# sim800c_gsm_dev_board.net
KiCad netlist of a schematic drawn in EAGLE
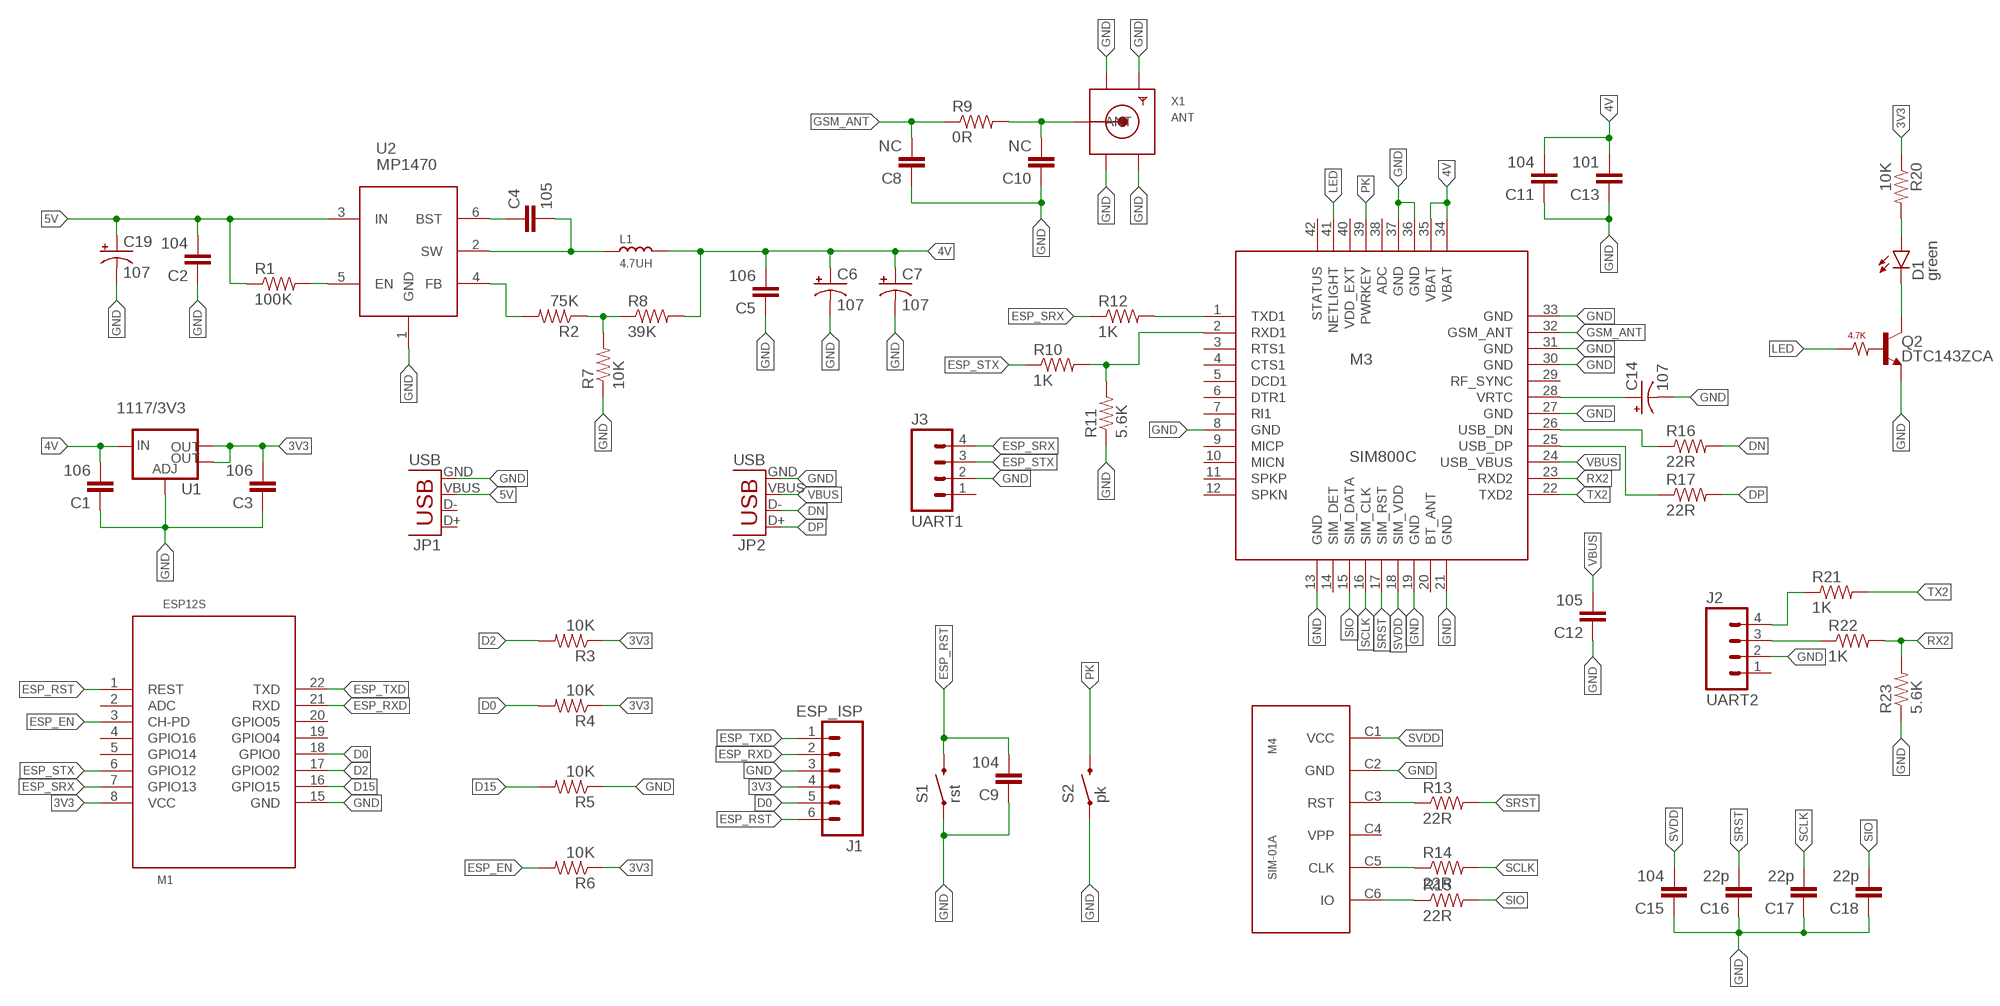
[diagram p0: schematic, sheet 1]

(export (version "E")
  (design (tool "Eeschema 10.0.6"))
  (components
    (comp (ref "C1")
      (value "106")
      (footprint "eagle-import:0603-CAP")
      (libsource (lib "eagle-import") (part "CAP0603-CAP"))
    )
    (comp (ref "C2")
      (value "104")
      (footprint "eagle-import:0603-CAP")
      (libsource (lib "eagle-import") (part "CAP0603-CAP"))
    )
    (comp (ref "C3")
      (value "106")
      (footprint "eagle-import:0603-CAP")
      (libsource (lib "eagle-import") (part "CAP0603-CAP"))
    )
    (comp (ref "C4")
      (value "105")
      (footprint "eagle-import:0603-CAP")
      (libsource (lib "eagle-import") (part "CAP0603-CAP"))
    )
    (comp (ref "C5")
      (value "106")
      (footprint "eagle-import:0603-CAP")
      (libsource (lib "eagle-import") (part "CAP0603-CAP"))
    )
    (comp (ref "C6")
      (value "107")
      (footprint "eagle-import:EIA3528")
      (libsource (lib "eagle-import") (part "CAP_POL3528"))
    )
    (comp (ref "C7")
      (value "107")
      (footprint "eagle-import:EIA3528")
      (libsource (lib "eagle-import") (part "CAP_POL3528"))
    )
    (comp (ref "C8")
      (value "NC")
      (footprint "eagle-import:C0402")
      (libsource (lib "eagle-import") (part "CAP-SEEED-0402"))
    )
    (comp (ref "C9")
      (value "104")
      (footprint "eagle-import:C0402")
      (libsource (lib "eagle-import") (part "CAP-SEEED-0402"))
    )
    (comp (ref "C10")
      (value "NC")
      (footprint "eagle-import:C0402")
      (libsource (lib "eagle-import") (part "CAP-SEEED-0402"))
    )
    (comp (ref "C11")
      (value "104")
      (footprint "eagle-import:C0402")
      (libsource (lib "eagle-import") (part "CAP-SEEED-0402"))
    )
    (comp (ref "C12")
      (value "105")
      (footprint "eagle-import:0603-CAP")
      (libsource (lib "eagle-import") (part "CAP0603-CAP"))
    )
    (comp (ref "C13")
      (value "101")
      (footprint "eagle-import:C0402")
      (libsource (lib "eagle-import") (part "CAP-SEEED-0402"))
    )
    (comp (ref "C14")
      (value "107")
      (footprint "eagle-import:EIA3528")
      (libsource (lib "eagle-import") (part "CAP_POL3528"))
    )
    (comp (ref "C15")
      (value "104")
      (footprint "eagle-import:C0402")
      (libsource (lib "eagle-import") (part "CAP-SEEED-0402"))
    )
    (comp (ref "C16")
      (value "22p")
      (footprint "eagle-import:C0402")
      (libsource (lib "eagle-import") (part "CAP-SEEED-0402"))
    )
    (comp (ref "C17")
      (value "22p")
      (footprint "eagle-import:C0402")
      (libsource (lib "eagle-import") (part "CAP-SEEED-0402"))
    )
    (comp (ref "C18")
      (value "22p")
      (footprint "eagle-import:C0402")
      (libsource (lib "eagle-import") (part "CAP-SEEED-0402"))
    )
    (comp (ref "C19")
      (value "107")
      (footprint "eagle-import:EIA3528")
      (libsource (lib "eagle-import") (part "CAP_POL3528"))
    )
    (comp (ref "D1")
      (value "green")
      (footprint "eagle-import:LED-0603-SEEED")
      (libsource (lib "eagle-import") (part "LED-SEEED-0603"))
    )
    (comp (ref "J1")
      (value "ESP_ISP")
      (footprint "eagle-import:1X06_NO_SILK")
      (libsource (lib "eagle-import") (part "M06NO_SILK_FEMALE_PTH"))
    )
    (comp (ref "J2")
      (value "UART2")
      (footprint "eagle-import:1X04_NO_SILK_ALL_ROUND")
      (libsource (lib "eagle-import") (part "M04NO_SILK_ALL_ROUND"))
    )
    (comp (ref "J3")
      (value "UART1")
      (footprint "eagle-import:1X04_NO_SILK_ALL_ROUND")
      (libsource (lib "eagle-import") (part "M04NO_SILK_ALL_ROUND"))
    )
    (comp (ref "JP1")
      (value "USB")
      (footprint "eagle-import:MICROUSB-U-F-M5DD-Y-1")
      (libsource (lib "eagle-import") (part "USB"))
    )
    (comp (ref "JP2")
      (value "USB")
      (footprint "eagle-import:MICROUSB-U-F-M5DD-Y-1")
      (libsource (lib "eagle-import") (part "USB"))
    )
    (comp (ref "L1")
      (value "4.7UH")
      (footprint "eagle-import:SMD-2P-5.0X5.0X2.0MM")
      (fields (field (name "MPN") "SWPA5020S220MT"))
      (libsource (lib "eagle-import") (part "SMD-INDUCTOR-200UH-20%(2P-5X5MM)"))
    )
    (comp (ref "M1")
      (value "ESP12S")
      (footprint "eagle-import:LGA22-2.0-24X16MM-SIMPLE")
      (libsource (lib "eagle-import") (part "MODULE-WIFI-ESP8266-12E-SIMPLE"))
    )
    (comp (ref "M3")
      (value "SIM800C")
      (footprint "eagle-import:SIM800C")
      (libsource (lib "eagle-import") (part "SIM800C"))
    )
    (comp (ref "M4")
      (value "SIM-01A")
      (footprint "eagle-import:SIM-01A")
      (libsource (lib "eagle-import") (part "SIM-01A"))
    )
    (comp (ref "Q2")
      (value "DTC143ZCA")
      (footprint "eagle-import:SOT23-3")
      (libsource (lib "eagle-import") (part "TRANS_NPN_RES-DDTD142TC-7-F"))
    )
    (comp (ref "R1")
      (value "100K")
      (footprint "eagle-import:R0402")
      (libsource (lib "eagle-import") (part "RESISTOR-SEEED-0402"))
    )
    (comp (ref "R2")
      (value "75K")
      (footprint "eagle-import:R0402")
      (libsource (lib "eagle-import") (part "RESISTOR-SEEED-0402"))
    )
    (comp (ref "R3")
      (value "10K")
      (footprint "eagle-import:R0402")
      (libsource (lib "eagle-import") (part "RESISTOR-SEEED-0402"))
    )
    (comp (ref "R4")
      (value "10K")
      (footprint "eagle-import:R0402")
      (libsource (lib "eagle-import") (part "RESISTOR-SEEED-0402"))
    )
    (comp (ref "R5")
      (value "10K")
      (footprint "eagle-import:R0402")
      (libsource (lib "eagle-import") (part "RESISTOR-SEEED-0402"))
    )
    (comp (ref "R6")
      (value "10K")
      (footprint "eagle-import:R0402")
      (libsource (lib "eagle-import") (part "RESISTOR-SEEED-0402"))
    )
    (comp (ref "R7")
      (value "10K")
      (footprint "eagle-import:R0402")
      (libsource (lib "eagle-import") (part "RESISTOR-SEEED-0402"))
    )
    (comp (ref "R8")
      (value "39K")
      (footprint "eagle-import:R0402")
      (libsource (lib "eagle-import") (part "RESISTOR-SEEED-0402"))
    )
    (comp (ref "R9")
      (value "0R")
      (footprint "eagle-import:R0402")
      (libsource (lib "eagle-import") (part "RESISTOR-SEEED-0402"))
    )
    (comp (ref "R10")
      (value "1K")
      (footprint "eagle-import:R0402")
      (libsource (lib "eagle-import") (part "RESISTOR-SEEED-0402"))
    )
    (comp (ref "R11")
      (value "5.6K")
      (footprint "eagle-import:R0402")
      (libsource (lib "eagle-import") (part "RESISTOR-SEEED-0402"))
    )
    (comp (ref "R12")
      (value "1K")
      (footprint "eagle-import:R0402")
      (libsource (lib "eagle-import") (part "RESISTOR-SEEED-0402"))
    )
    (comp (ref "R13")
      (value "22R")
      (footprint "eagle-import:R0402")
      (libsource (lib "eagle-import") (part "RESISTOR-SEEED-0402"))
    )
    (comp (ref "R14")
      (value "22R")
      (footprint "eagle-import:R0402")
      (libsource (lib "eagle-import") (part "RESISTOR-SEEED-0402"))
    )
    (comp (ref "R15")
      (value "22R")
      (footprint "eagle-import:R0402")
      (libsource (lib "eagle-import") (part "RESISTOR-SEEED-0402"))
    )
    (comp (ref "R16")
      (value "22R")
      (footprint "eagle-import:R0402")
      (libsource (lib "eagle-import") (part "RESISTOR-SEEED-0402"))
    )
    (comp (ref "R17")
      (value "22R")
      (footprint "eagle-import:R0402")
      (libsource (lib "eagle-import") (part "RESISTOR-SEEED-0402"))
    )
    (comp (ref "R20")
      (value "10K")
      (footprint "eagle-import:R0402")
      (libsource (lib "eagle-import") (part "RESISTOR-SEEED-0402"))
    )
    (comp (ref "R21")
      (value "1K")
      (footprint "eagle-import:R0402")
      (libsource (lib "eagle-import") (part "RESISTOR-SEEED-0402"))
    )
    (comp (ref "R22")
      (value "1K")
      (footprint "eagle-import:R0402")
      (libsource (lib "eagle-import") (part "RESISTOR-SEEED-0402"))
    )
    (comp (ref "R23")
      (value "5.6K")
      (footprint "eagle-import:R0402")
      (libsource (lib "eagle-import") (part "RESISTOR-SEEED-0402"))
    )
    (comp (ref "S1")
      (value "rst")
      (footprint "eagle-import:TACTILE_SWITCH_TALL")
      (libsource (lib "eagle-import") (part "SWITCH-MOMENTARY-2SMD-4"))
    )
    (comp (ref "S2")
      (value "pk")
      (footprint "eagle-import:TACTILE_SWITCH_TALL")
      (libsource (lib "eagle-import") (part "SWITCH-MOMENTARY-2SMD-4"))
    )
    (comp (ref "U1")
      (value "1117/3V3")
      (footprint "eagle-import:SOT223")
      (libsource (lib "eagle-import") (part "AMS1117SOT223"))
    )
    (comp (ref "U2")
      (value "MP1470")
      (footprint "eagle-import:SOT23-6")
      (libsource (lib "eagle-import") (part "MP1470"))
    )
    (comp (ref "X1")
      (value "ANT")
      (footprint "eagle-import:SMA90_DIP")
      (libsource (lib "eagle-import") (part "SMACONNECTOR"))
    )
  )
  (nets
    (net (code "1") (name "3V3") (class "Default")
      (node (ref "C3") (pin "2") (pinfunction "2_2") (pintype "passive"))
      (node (ref "J1") (pin "4") (pinfunction "4_4") (pintype "passive"))
      (node (ref "M1") (pin "8") (pinfunction "VCC_8") (pintype "bidirectional"))
      (node (ref "R20") (pin "1") (pinfunction "1_1") (pintype "passive"))
      (node (ref "R3") (pin "1") (pinfunction "1_1") (pintype "passive"))
      (node (ref "R4") (pin "1") (pinfunction "1_1") (pintype "passive"))
      (node (ref "R6") (pin "1") (pinfunction "1_1") (pintype "passive"))
      (node (ref "U1") (pin "2") (pinfunction "OUT_2") (pintype "output"))
      (node (ref "U1") (pin "4") (pinfunction "OUT_4") (pintype "output"))
    )
    (net (code "2") (name "4V") (class "Default")
      (node (ref "C1") (pin "2") (pinfunction "2_2") (pintype "passive"))
      (node (ref "C11") (pin "2") (pinfunction "2_2") (pintype "passive"))
      (node (ref "C13") (pin "2") (pinfunction "2_2") (pintype "passive"))
      (node (ref "C5") (pin "2") (pinfunction "2_2") (pintype "passive"))
      (node (ref "C6") (pin "A") (pinfunction "+_A") (pintype "passive"))
      (node (ref "C7") (pin "A") (pinfunction "+_A") (pintype "passive"))
      (node (ref "L1") (pin "2") (pinfunction "2_2") (pintype "passive"))
      (node (ref "M3") (pin "34") (pinfunction "VBAT_34") (pintype "bidirectional"))
      (node (ref "M3") (pin "35") (pinfunction "VBAT_35") (pintype "bidirectional"))
      (node (ref "R8") (pin "2") (pinfunction "2_2") (pintype "passive"))
      (node (ref "U1") (pin "3") (pinfunction "IN_3") (pintype "input"))
    )
    (net (code "3") (name "5V") (class "Default")
      (node (ref "C19") (pin "A") (pinfunction "+_A") (pintype "passive"))
      (node (ref "C2") (pin "2") (pinfunction "2_2") (pintype "passive"))
      (node (ref "JP1") (pin "VBUS") (pinfunction "VBUS_VBUS") (pintype "bidirectional"))
      (node (ref "R1") (pin "1") (pinfunction "1_1") (pintype "passive"))
      (node (ref "U2") (pin "3") (pinfunction "IN_3") (pintype "bidirectional"))
    )
    (net (code "4") (name "D0") (class "Default")
      (node (ref "J1") (pin "5") (pinfunction "5_5") (pintype "passive"))
      (node (ref "M1") (pin "18") (pinfunction "GPIO0_18") (pintype "bidirectional"))
      (node (ref "R4") (pin "2") (pinfunction "2_2") (pintype "passive"))
    )
    (net (code "5") (name "D2") (class "Default")
      (node (ref "M1") (pin "17") (pinfunction "GPIO02_17") (pintype "bidirectional"))
      (node (ref "R3") (pin "2") (pinfunction "2_2") (pintype "passive"))
    )
    (net (code "6") (name "D15") (class "Default")
      (node (ref "M1") (pin "16") (pinfunction "GPIO15_16") (pintype "bidirectional"))
      (node (ref "R5") (pin "2") (pinfunction "2_2") (pintype "passive"))
    )
    (net (code "7") (name "DN") (class "Default")
      (node (ref "JP2") (pin "D-") (pinfunction "D-_D-") (pintype "bidirectional"))
      (node (ref "R16") (pin "2") (pinfunction "2_2") (pintype "passive"))
    )
    (net (code "8") (name "DP") (class "Default")
      (node (ref "JP2") (pin "D+") (pinfunction "D+_D+") (pintype "bidirectional"))
      (node (ref "R17") (pin "2") (pinfunction "2_2") (pintype "passive"))
    )
    (net (code "9") (name "ESP_EN") (class "Default")
      (node (ref "M1") (pin "3") (pinfunction "CH-PD_3") (pintype "bidirectional"))
      (node (ref "R6") (pin "2") (pinfunction "2_2") (pintype "passive"))
    )
    (net (code "10") (name "ESP_RST") (class "Default")
      (node (ref "C9") (pin "2") (pinfunction "2_2") (pintype "passive"))
      (node (ref "J1") (pin "6") (pinfunction "6_6") (pintype "passive"))
      (node (ref "M1") (pin "1") (pinfunction "REST_1") (pintype "bidirectional"))
      (node (ref "S1") (pin "B2") (pinfunction "2_B2") (pintype "passive"))
    )
    (net (code "11") (name "ESP_RXD") (class "Default")
      (node (ref "J1") (pin "2") (pinfunction "2_2") (pintype "passive"))
      (node (ref "M1") (pin "21") (pinfunction "RXD_21") (pintype "bidirectional"))
    )
    (net (code "12") (name "ESP_SRX") (class "Default")
      (node (ref "J3") (pin "4") (pinfunction "4_4") (pintype "passive"))
      (node (ref "M1") (pin "7") (pinfunction "GPIO13_7") (pintype "bidirectional"))
      (node (ref "R12") (pin "1") (pinfunction "1_1") (pintype "passive"))
    )
    (net (code "13") (name "ESP_STX") (class "Default")
      (node (ref "J3") (pin "3") (pinfunction "3_3") (pintype "passive"))
      (node (ref "M1") (pin "6") (pinfunction "GPIO12_6") (pintype "bidirectional"))
      (node (ref "R10") (pin "1") (pinfunction "1_1") (pintype "passive"))
    )
    (net (code "14") (name "ESP_TXD") (class "Default")
      (node (ref "J1") (pin "1") (pinfunction "1_1") (pintype "passive"))
      (node (ref "M1") (pin "22") (pinfunction "TXD_22") (pintype "bidirectional"))
    )
    (net (code "15") (name "GND") (class "Default")
      (node (ref "C1") (pin "1") (pinfunction "1_1") (pintype "passive"))
      (node (ref "C10") (pin "1") (pinfunction "1_1") (pintype "passive"))
      (node (ref "C11") (pin "1") (pinfunction "1_1") (pintype "passive"))
      (node (ref "C12") (pin "1") (pinfunction "1_1") (pintype "passive"))
      (node (ref "C13") (pin "1") (pinfunction "1_1") (pintype "passive"))
      (node (ref "C14") (pin "C") (pinfunction "-_C") (pintype "passive"))
      (node (ref "C15") (pin "1") (pinfunction "1_1") (pintype "passive"))
      (node (ref "C16") (pin "1") (pinfunction "1_1") (pintype "passive"))
      (node (ref "C17") (pin "1") (pinfunction "1_1") (pintype "passive"))
      (node (ref "C18") (pin "1") (pinfunction "1_1") (pintype "passive"))
      (node (ref "C19") (pin "C") (pinfunction "-_C") (pintype "passive"))
      (node (ref "C2") (pin "1") (pinfunction "1_1") (pintype "passive"))
      (node (ref "C3") (pin "1") (pinfunction "1_1") (pintype "passive"))
      (node (ref "C5") (pin "1") (pinfunction "1_1") (pintype "passive"))
      (node (ref "C6") (pin "C") (pinfunction "-_C") (pintype "passive"))
      (node (ref "C7") (pin "C") (pinfunction "-_C") (pintype "passive"))
      (node (ref "C8") (pin "1") (pinfunction "1_1") (pintype "passive"))
      (node (ref "C9") (pin "1") (pinfunction "1_1") (pintype "passive"))
      (node (ref "J1") (pin "3") (pinfunction "3_3") (pintype "passive"))
      (node (ref "J2") (pin "2") (pinfunction "2_2") (pintype "passive"))
      (node (ref "J3") (pin "2") (pinfunction "2_2") (pintype "passive"))
      (node (ref "JP1") (pin "GND") (pinfunction "GND_GND") (pintype "bidirectional"))
      (node (ref "JP2") (pin "GND") (pinfunction "GND_GND") (pintype "bidirectional"))
      (node (ref "M1") (pin "15") (pinfunction "GND_15") (pintype "bidirectional"))
      (node (ref "M3") (pin "13") (pinfunction "GND_13") (pintype "bidirectional"))
      (node (ref "M3") (pin "19") (pinfunction "GND_19") (pintype "bidirectional"))
      (node (ref "M3") (pin "21") (pinfunction "GND_21") (pintype "bidirectional"))
      (node (ref "M3") (pin "27") (pinfunction "GND_27") (pintype "bidirectional"))
      (node (ref "M3") (pin "30") (pinfunction "GND_30") (pintype "bidirectional"))
      (node (ref "M3") (pin "31") (pinfunction "GND_31") (pintype "bidirectional"))
      (node (ref "M3") (pin "33") (pinfunction "GND_33") (pintype "bidirectional"))
      (node (ref "M3") (pin "36") (pinfunction "GND_36") (pintype "bidirectional"))
      (node (ref "M3") (pin "37") (pinfunction "GND_37") (pintype "bidirectional"))
      (node (ref "M3") (pin "8") (pinfunction "GND_8") (pintype "bidirectional"))
      (node (ref "M4") (pin "C2") (pinfunction "GND_C2") (pintype "bidirectional"))
      (node (ref "Q2") (pin "2") (pinfunction "E_2") (pintype "passive"))
      (node (ref "R11") (pin "1") (pinfunction "1_1") (pintype "passive"))
      (node (ref "R23") (pin "1") (pinfunction "1_1") (pintype "passive"))
      (node (ref "R5") (pin "1") (pinfunction "1_1") (pintype "passive"))
      (node (ref "R7") (pin "1") (pinfunction "1_1") (pintype "passive"))
      (node (ref "S1") (pin "A2") (pinfunction "1_A2") (pintype "passive"))
      (node (ref "S2") (pin "A2") (pinfunction "1_A2") (pintype "passive"))
      (node (ref "U1") (pin "1") (pinfunction "ADJ_1") (pintype "input"))
      (node (ref "U2") (pin "1") (pinfunction "GND_1") (pintype "bidirectional"))
      (node (ref "X1") (pin "GND1") (pinfunction "GND1_GND1") (pintype "power_in"))
      (node (ref "X1") (pin "GND2") (pinfunction "GND2_GND2") (pintype "power_in"))
      (node (ref "X1") (pin "GND3") (pinfunction "GND3_GND3") (pintype "power_in"))
      (node (ref "X1") (pin "GND4") (pinfunction "GND4_GND4") (pintype "power_in"))
    )
    (net (code "16") (name "GSM_ANT") (class "Default")
      (node (ref "C8") (pin "2") (pinfunction "2_2") (pintype "passive"))
      (node (ref "M3") (pin "32") (pinfunction "GSM_ANT_32") (pintype "bidirectional"))
      (node (ref "R9") (pin "1") (pinfunction "1_1") (pintype "passive"))
    )
    (net (code "17") (name "LED") (class "Default")
      (node (ref "M3") (pin "41") (pinfunction "NETLIGHT_41") (pintype "bidirectional"))
      (node (ref "Q2") (pin "1") (pinfunction "B_1") (pintype "passive"))
    )
    (net (code "18") (name "Net-(C14-+)") (class "Default")
      (node (ref "C14") (pin "A") (pinfunction "+_A") (pintype "passive"))
      (node (ref "M3") (pin "28") (pinfunction "VRTC_28") (pintype "bidirectional"))
    )
    (net (code "19") (name "Net-(D1-A)") (class "Default")
      (node (ref "D1") (pin "+") (pinfunction "A_+") (pintype "passive"))
      (node (ref "R20") (pin "2") (pinfunction "2_2") (pintype "passive"))
    )
    (net (code "20") (name "Net-(D1-C)") (class "Default")
      (node (ref "D1") (pin "-") (pinfunction "C_-") (pintype "passive"))
      (node (ref "Q2") (pin "3") (pinfunction "C_3") (pintype "passive"))
    )
    (net (code "21") (name "Net-(J2-Pad3)") (class "Default")
      (node (ref "J2") (pin "3") (pinfunction "3_3") (pintype "passive"))
      (node (ref "R22") (pin "1") (pinfunction "1_1") (pintype "passive"))
    )
    (net (code "22") (name "Net-(J2-Pad4)") (class "Default")
      (node (ref "J2") (pin "4") (pinfunction "4_4") (pintype "passive"))
      (node (ref "R21") (pin "1") (pinfunction "1_1") (pintype "passive"))
    )
    (net (code "23") (name "Net-(M3-RXD1)") (class "Default")
      (node (ref "M3") (pin "2") (pinfunction "RXD1_2") (pintype "bidirectional"))
      (node (ref "R10") (pin "2") (pinfunction "2_2") (pintype "passive"))
      (node (ref "R11") (pin "2") (pinfunction "2_2") (pintype "passive"))
    )
    (net (code "24") (name "Net-(M3-TXD1)") (class "Default")
      (node (ref "M3") (pin "1") (pinfunction "TXD1_1") (pintype "bidirectional"))
      (node (ref "R12") (pin "2") (pinfunction "2_2") (pintype "passive"))
    )
    (net (code "25") (name "Net-(M3-USB_DN)") (class "Default")
      (node (ref "M3") (pin "26") (pinfunction "USB_DN_26") (pintype "bidirectional"))
      (node (ref "R16") (pin "1") (pinfunction "1_1") (pintype "passive"))
    )
    (net (code "26") (name "Net-(M3-USB_DP)") (class "Default")
      (node (ref "M3") (pin "25") (pinfunction "USB_DP_25") (pintype "bidirectional"))
      (node (ref "R17") (pin "1") (pinfunction "1_1") (pintype "passive"))
    )
    (net (code "27") (name "Net-(M4-CLK)") (class "Default")
      (node (ref "M4") (pin "C5") (pinfunction "CLK_C5") (pintype "bidirectional"))
      (node (ref "R14") (pin "1") (pinfunction "1_1") (pintype "passive"))
    )
    (net (code "28") (name "Net-(M4-IO)") (class "Default")
      (node (ref "M4") (pin "C6") (pinfunction "IO_C6") (pintype "bidirectional"))
      (node (ref "R15") (pin "1") (pinfunction "1_1") (pintype "passive"))
    )
    (net (code "29") (name "Net-(M4-RST)") (class "Default")
      (node (ref "M4") (pin "C3") (pinfunction "RST_C3") (pintype "bidirectional"))
      (node (ref "R13") (pin "1") (pinfunction "1_1") (pintype "passive"))
    )
    (net (code "30") (name "Net-(R2-Pad1)") (class "Default")
      (node (ref "R2") (pin "1") (pinfunction "1_1") (pintype "passive"))
      (node (ref "R7") (pin "2") (pinfunction "2_2") (pintype "passive"))
      (node (ref "R8") (pin "1") (pinfunction "1_1") (pintype "passive"))
    )
    (net (code "31") (name "Net-(U2-BST)") (class "Default")
      (node (ref "C4") (pin "1") (pinfunction "1_1") (pintype "passive"))
      (node (ref "U2") (pin "6") (pinfunction "BST_6") (pintype "bidirectional"))
    )
    (net (code "32") (name "Net-(U2-EN)") (class "Default")
      (node (ref "R1") (pin "2") (pinfunction "2_2") (pintype "passive"))
      (node (ref "U2") (pin "5") (pinfunction "EN_5") (pintype "bidirectional"))
    )
    (net (code "33") (name "Net-(U2-FB)") (class "Default")
      (node (ref "R2") (pin "2") (pinfunction "2_2") (pintype "passive"))
      (node (ref "U2") (pin "4") (pinfunction "FB_4") (pintype "bidirectional"))
    )
    (net (code "34") (name "Net-(U2-SW)") (class "Default")
      (node (ref "C4") (pin "2") (pinfunction "2_2") (pintype "passive"))
      (node (ref "L1") (pin "1") (pinfunction "1_1") (pintype "passive"))
      (node (ref "U2") (pin "2") (pinfunction "SW_2") (pintype "bidirectional"))
    )
    (net (code "35") (name "Net-(X1-ANT)") (class "Default")
      (node (ref "C10") (pin "2") (pinfunction "2_2") (pintype "passive"))
      (node (ref "R9") (pin "2") (pinfunction "2_2") (pintype "passive"))
      (node (ref "X1") (pin "ANTENNA") (pinfunction "ANT_ANTENNA") (pintype "bidirectional"))
    )
    (net (code "36") (name "PK") (class "Default")
      (node (ref "M3") (pin "39") (pinfunction "PWRKEY_39") (pintype "bidirectional"))
      (node (ref "S2") (pin "B2") (pinfunction "2_B2") (pintype "passive"))
    )
    (net (code "37") (name "RX2") (class "Default")
      (node (ref "M3") (pin "23") (pinfunction "RXD2_23") (pintype "bidirectional"))
      (node (ref "R22") (pin "2") (pinfunction "2_2") (pintype "passive"))
      (node (ref "R23") (pin "2") (pinfunction "2_2") (pintype "passive"))
    )
    (net (code "38") (name "SCLK") (class "Default")
      (node (ref "C17") (pin "2") (pinfunction "2_2") (pintype "passive"))
      (node (ref "M3") (pin "16") (pinfunction "SIM_CLK_16") (pintype "bidirectional"))
      (node (ref "R14") (pin "2") (pinfunction "2_2") (pintype "passive"))
    )
    (net (code "39") (name "SIO") (class "Default")
      (node (ref "C18") (pin "2") (pinfunction "2_2") (pintype "passive"))
      (node (ref "M3") (pin "15") (pinfunction "SIM_DATA_15") (pintype "bidirectional"))
      (node (ref "R15") (pin "2") (pinfunction "2_2") (pintype "passive"))
    )
    (net (code "40") (name "SRST") (class "Default")
      (node (ref "C16") (pin "2") (pinfunction "2_2") (pintype "passive"))
      (node (ref "M3") (pin "17") (pinfunction "SIM_RST_17") (pintype "bidirectional"))
      (node (ref "R13") (pin "2") (pinfunction "2_2") (pintype "passive"))
    )
    (net (code "41") (name "SVDD") (class "Default")
      (node (ref "C15") (pin "2") (pinfunction "2_2") (pintype "passive"))
      (node (ref "M3") (pin "18") (pinfunction "SIM_VDD_18") (pintype "bidirectional"))
      (node (ref "M4") (pin "C1") (pinfunction "VCC_C1") (pintype "bidirectional"))
    )
    (net (code "42") (name "TX2") (class "Default")
      (node (ref "M3") (pin "22") (pinfunction "TXD2_22") (pintype "bidirectional"))
      (node (ref "R21") (pin "2") (pinfunction "2_2") (pintype "passive"))
    )
    (net (code "43") (name "VBUS") (class "Default")
      (node (ref "C12") (pin "2") (pinfunction "2_2") (pintype "passive"))
      (node (ref "JP2") (pin "VBUS") (pinfunction "VBUS_VBUS") (pintype "bidirectional"))
      (node (ref "M3") (pin "24") (pinfunction "USB_VBUS_24") (pintype "bidirectional"))
    )
    (net (code "44") (name "unconnected-(J2-Pad1)") (class "Default")
      (node (ref "J2") (pin "1") (pinfunction "1_1") (pintype "passive"))
    )
    (net (code "45") (name "unconnected-(J3-Pad1)") (class "Default")
      (node (ref "J3") (pin "1") (pinfunction "1_1") (pintype "passive"))
    )
    (net (code "46") (name "unconnected-(JP1-PadD+)") (class "Default")
      (node (ref "JP1") (pin "D+") (pinfunction "D+_D+") (pintype "bidirectional"))
    )
    (net (code "47") (name "unconnected-(JP1-PadD-)") (class "Default")
      (node (ref "JP1") (pin "D-") (pinfunction "D-_D-") (pintype "bidirectional"))
    )
    (net (code "48") (name "unconnected-(M1-ADC-Pad2)") (class "Default")
      (node (ref "M1") (pin "2") (pinfunction "ADC_2") (pintype "bidirectional"))
    )
    (net (code "49") (name "unconnected-(M1-GPIO04-Pad19)") (class "Default")
      (node (ref "M1") (pin "19") (pinfunction "GPIO04_19") (pintype "bidirectional"))
    )
    (net (code "50") (name "unconnected-(M1-GPIO05-Pad20)") (class "Default")
      (node (ref "M1") (pin "20") (pinfunction "GPIO05_20") (pintype "bidirectional"))
    )
    (net (code "51") (name "unconnected-(M1-GPIO14-Pad5)") (class "Default")
      (node (ref "M1") (pin "5") (pinfunction "GPIO14_5") (pintype "bidirectional"))
    )
    (net (code "52") (name "unconnected-(M1-GPIO16-Pad4)") (class "Default")
      (node (ref "M1") (pin "4") (pinfunction "GPIO16_4") (pintype "bidirectional"))
    )
    (net (code "53") (name "unconnected-(M3-ADC-Pad38)") (class "Default")
      (node (ref "M3") (pin "38") (pinfunction "ADC_38") (pintype "bidirectional"))
    )
    (net (code "54") (name "unconnected-(M3-BT_ANT-Pad20)") (class "Default")
      (node (ref "M3") (pin "20") (pinfunction "BT_ANT_20") (pintype "bidirectional"))
    )
    (net (code "55") (name "unconnected-(M3-CTS1-Pad4)") (class "Default")
      (node (ref "M3") (pin "4") (pinfunction "CTS1_4") (pintype "bidirectional"))
    )
    (net (code "56") (name "unconnected-(M3-DCD1-Pad5)") (class "Default")
      (node (ref "M3") (pin "5") (pinfunction "DCD1_5") (pintype "bidirectional"))
    )
    (net (code "57") (name "unconnected-(M3-DTR1-Pad6)") (class "Default")
      (node (ref "M3") (pin "6") (pinfunction "DTR1_6") (pintype "bidirectional"))
    )
    (net (code "58") (name "unconnected-(M3-MICN-Pad10)") (class "Default")
      (node (ref "M3") (pin "10") (pinfunction "MICN_10") (pintype "bidirectional"))
    )
    (net (code "59") (name "unconnected-(M3-MICP-Pad9)") (class "Default")
      (node (ref "M3") (pin "9") (pinfunction "MICP_9") (pintype "bidirectional"))
    )
    (net (code "60") (name "unconnected-(M3-RF_SYNC-Pad29)") (class "Default")
      (node (ref "M3") (pin "29") (pinfunction "RF_SYNC_29") (pintype "bidirectional"))
    )
    (net (code "61") (name "unconnected-(M3-RI1-Pad7)") (class "Default")
      (node (ref "M3") (pin "7") (pinfunction "RI1_7") (pintype "bidirectional"))
    )
    (net (code "62") (name "unconnected-(M3-RTS1-Pad3)") (class "Default")
      (node (ref "M3") (pin "3") (pinfunction "RTS1_3") (pintype "bidirectional"))
    )
    (net (code "63") (name "unconnected-(M3-SIM_DET-Pad14)") (class "Default")
      (node (ref "M3") (pin "14") (pinfunction "SIM_DET_14") (pintype "bidirectional"))
    )
    (net (code "64") (name "unconnected-(M3-SPKN-Pad12)") (class "Default")
      (node (ref "M3") (pin "12") (pinfunction "SPKN_12") (pintype "bidirectional"))
    )
    (net (code "65") (name "unconnected-(M3-SPKP-Pad11)") (class "Default")
      (node (ref "M3") (pin "11") (pinfunction "SPKP_11") (pintype "bidirectional"))
    )
    (net (code "66") (name "unconnected-(M3-STATUS-Pad42)") (class "Default")
      (node (ref "M3") (pin "42") (pinfunction "STATUS_42") (pintype "bidirectional"))
    )
    (net (code "67") (name "unconnected-(M3-VDD_EXT-Pad40)") (class "Default")
      (node (ref "M3") (pin "40") (pinfunction "VDD_EXT_40") (pintype "bidirectional"))
    )
    (net (code "68") (name "unconnected-(M4-VPP-PadC4)") (class "Default")
      (node (ref "M4") (pin "C4") (pinfunction "VPP_C4") (pintype "bidirectional"))
    )
  )
)
